# IR.net
KiCad netlist of a schematic drawn in EAGLE
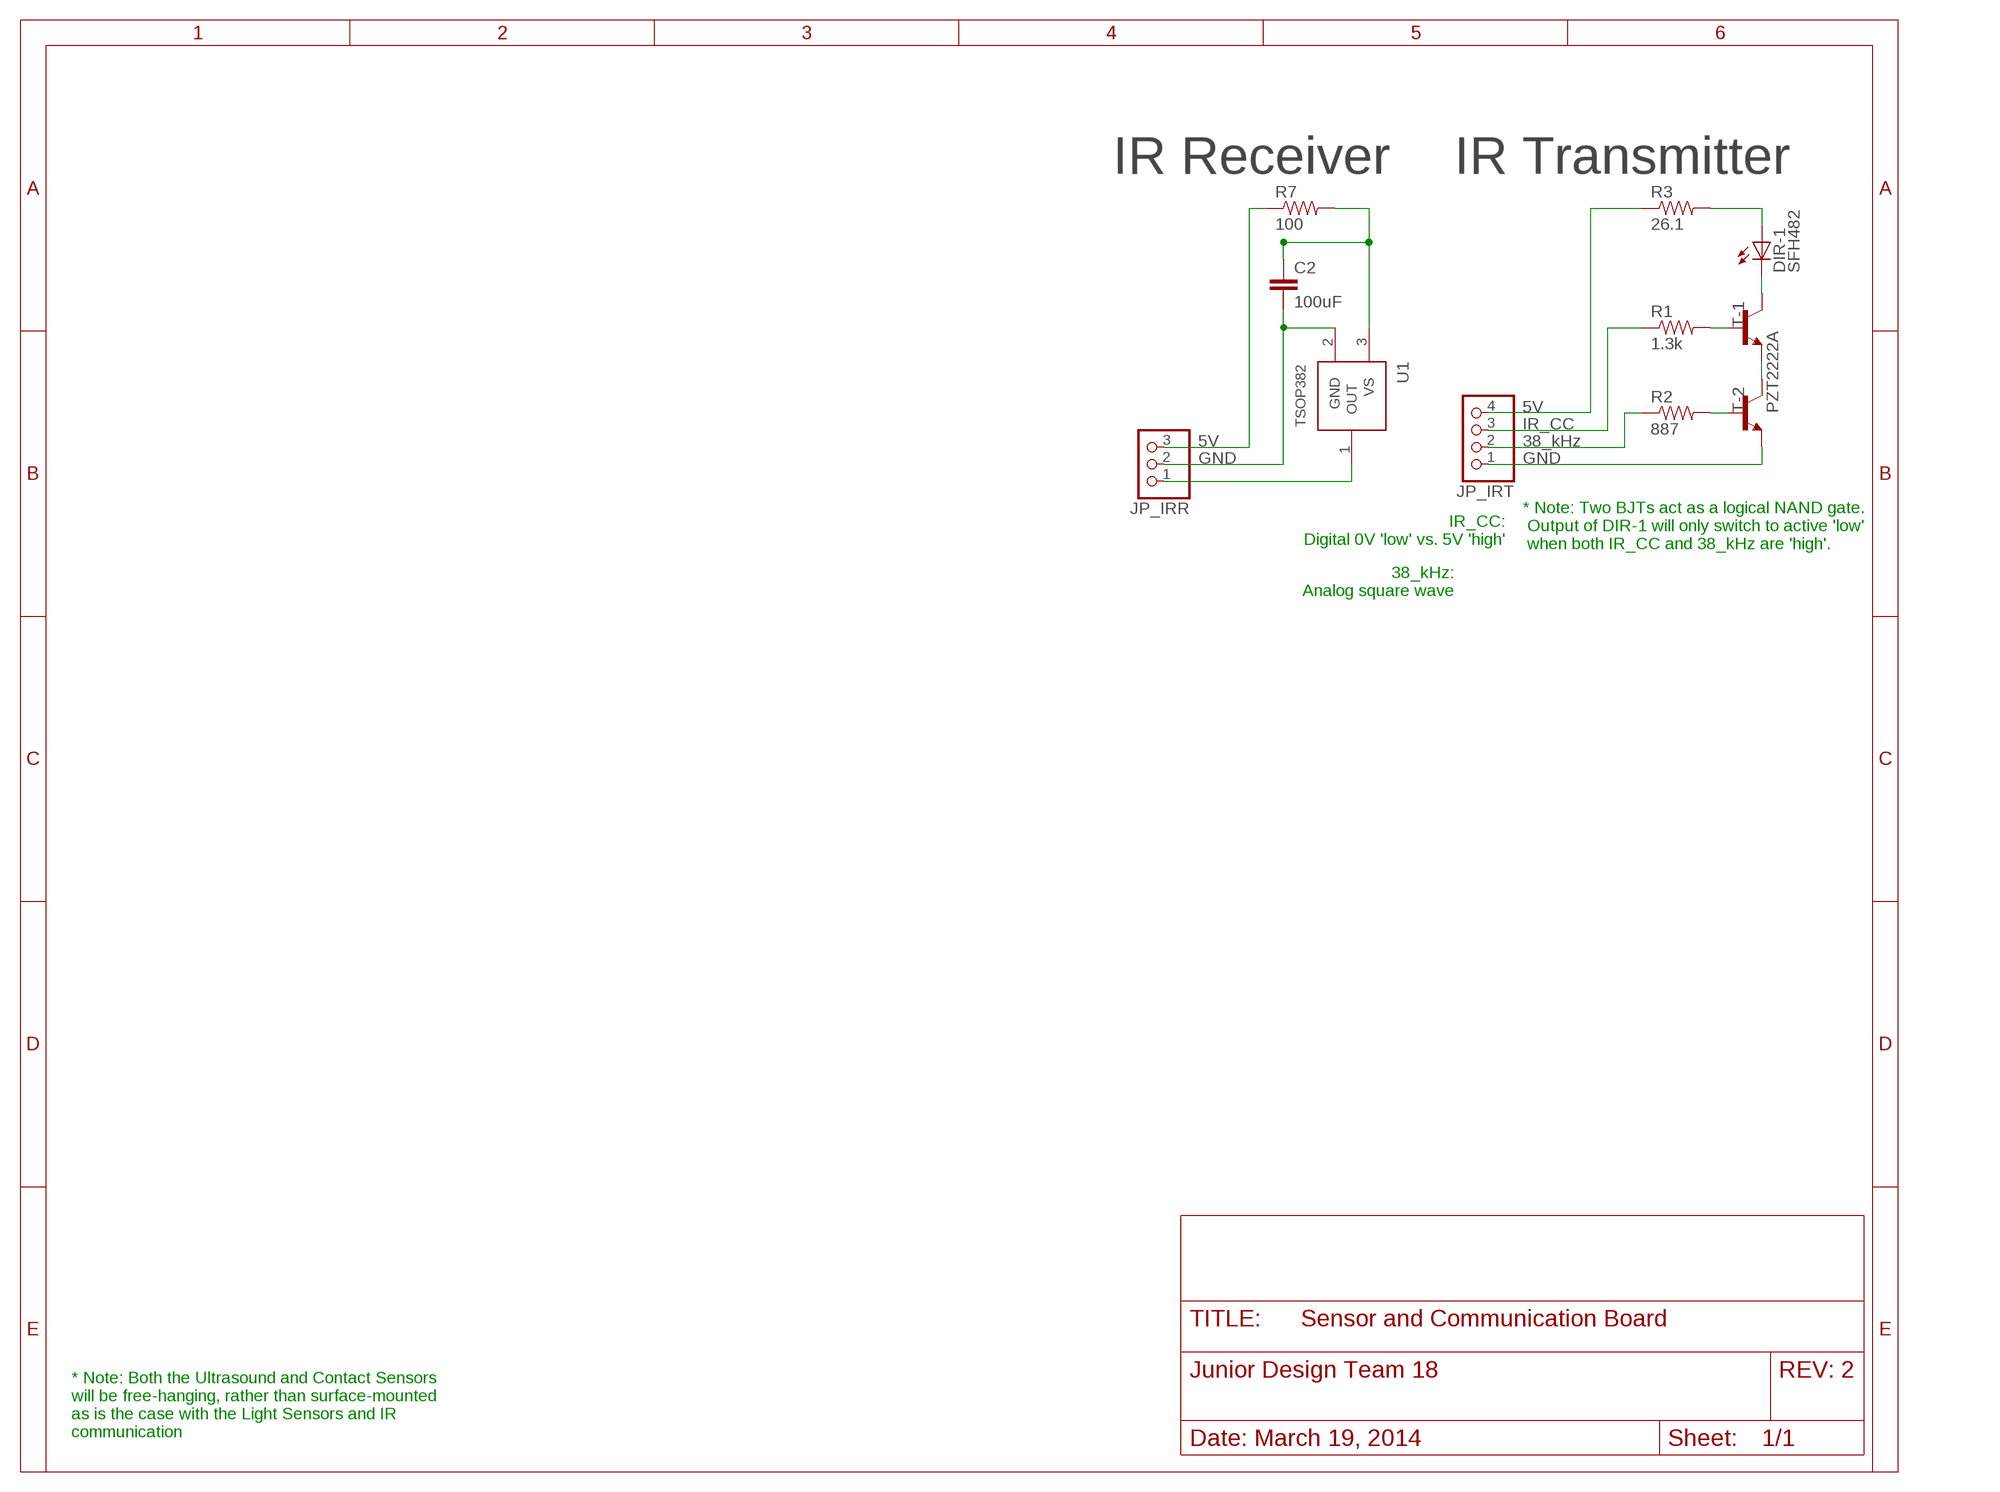
[diagram p0: schematic, sheet 1]

(export (version "E")
  (design (tool "Eeschema 10.0.6"))
  (components
    (comp (ref "C2")
      (value "100uF")
      (footprint "eagle-import:1206")
      (libsource (lib "eagle-import") (part "CAP1206"))
    )
    (comp (ref "DIR-1")
      (value "SFH482")
      (footprint "eagle-import:SFH482")
      (libsource (lib "eagle-import") (part "SFH482"))
    )
    (comp (ref "JP_IRR")
      (value "PINHD-1X3")
      (footprint "eagle-import:1X03")
      (libsource (lib "eagle-import") (part "PINHD-1X3"))
    )
    (comp (ref "JP_IRT")
      (value "PINHD-1X4")
      (footprint "eagle-import:1X04")
      (libsource (lib "eagle-import") (part "PINHD-1X4"))
    )
    (comp (ref "R1")
      (value "1.3k")
      (footprint "eagle-import:0805")
      (libsource (lib "eagle-import") (part "RESISTOR0805-RES"))
    )
    (comp (ref "R2")
      (value "887")
      (footprint "eagle-import:0805")
      (libsource (lib "eagle-import") (part "RESISTOR0805-RES"))
    )
    (comp (ref "R3")
      (value "26.1")
      (footprint "eagle-import:1206")
      (libsource (lib "eagle-import") (part "RESISTOR1206"))
    )
    (comp (ref "R7")
      (value "100")
      (footprint "eagle-import:0805")
      (libsource (lib "eagle-import") (part "RESISTOR0805-RES"))
    )
    (comp (ref "T-1")
      (value "PZT2222A")
      (footprint "eagle-import:SOT223")
      (libsource (lib "eagle-import") (part "PZT2222A"))
    )
    (comp (ref "T-2")
      (value "PZT2222A")
      (footprint "eagle-import:SOT223")
      (libsource (lib "eagle-import") (part "PZT2222A"))
    )
    (comp (ref "U1")
      (value "TSOP382")
      (footprint "eagle-import:TSOP382")
      (libsource (lib "eagle-import") (part "TSOP382"))
    )
  )
  (nets
    (net (code "1") (name "Net-(DIR-1-C)") (class "Default")
      (node (ref "DIR-1") (pin "K") (pinfunction "C_K") (pintype "passive"))
      (node (ref "T-1") (pin "2") (pinfunction "C_2") (pintype "passive"))
      (node (ref "T-1") (pin "4") (pinfunction "C_4") (pintype "passive"))
    )
    (net (code "2") (name "Net-(DIR-1-PadA)") (class "Default")
      (node (ref "DIR-1") (pin "A") (pinfunction "A_A") (pintype "passive"))
      (node (ref "R3") (pin "2") (pinfunction "2_2") (pintype "passive"))
    )
    (net (code "3") (name "Net-(JP_IRR-Pad3)") (class "Default")
      (node (ref "JP_IRR") (pin "3") (pinfunction "3_3") (pintype "passive"))
      (node (ref "R7") (pin "1") (pinfunction "1_1") (pintype "passive"))
    )
    (net (code "4") (name "Net-(JP_IRT-Pad2)") (class "Default")
      (node (ref "JP_IRT") (pin "2") (pinfunction "2_2") (pintype "passive"))
      (node (ref "R2") (pin "1") (pinfunction "1_1") (pintype "passive"))
    )
    (net (code "5") (name "Net-(JP_IRT-Pad3)") (class "Default")
      (node (ref "JP_IRT") (pin "3") (pinfunction "3_3") (pintype "passive"))
      (node (ref "R1") (pin "1") (pinfunction "1_1") (pintype "passive"))
    )
    (net (code "6") (name "Net-(JP_IRT-Pad4)") (class "Default")
      (node (ref "JP_IRT") (pin "4") (pinfunction "4_4") (pintype "passive"))
      (node (ref "R3") (pin "1") (pinfunction "1_1") (pintype "passive"))
    )
    (net (code "7") (name "Net-(T-1-B)") (class "Default")
      (node (ref "R1") (pin "2") (pinfunction "2_2") (pintype "passive"))
      (node (ref "T-1") (pin "1") (pinfunction "B_1") (pintype "passive"))
    )
    (net (code "8") (name "Net-(T-1-E)") (class "Default")
      (node (ref "T-1") (pin "3") (pinfunction "E_3") (pintype "passive"))
      (node (ref "T-2") (pin "2") (pinfunction "C_2") (pintype "passive"))
      (node (ref "T-2") (pin "4") (pinfunction "C_4") (pintype "passive"))
    )
    (net (code "9") (name "Net-(T-2-B)") (class "Default")
      (node (ref "R2") (pin "2") (pinfunction "2_2") (pintype "passive"))
      (node (ref "T-2") (pin "1") (pinfunction "B_1") (pintype "passive"))
    )
    (net (code "10") (name "Net-(T-2-E)") (class "Default")
      (node (ref "JP_IRT") (pin "1") (pinfunction "1_1") (pintype "passive"))
      (node (ref "T-2") (pin "3") (pinfunction "E_3") (pintype "passive"))
    )
    (net (code "11") (name "Net-(U1-GND)") (class "Default")
      (node (ref "C2") (pin "2") (pinfunction "2_2") (pintype "passive"))
      (node (ref "JP_IRR") (pin "2") (pinfunction "2_2") (pintype "passive"))
      (node (ref "U1") (pin "2") (pinfunction "GND_2") (pintype "bidirectional"))
    )
    (net (code "12") (name "Net-(U1-OUT)") (class "Default")
      (node (ref "JP_IRR") (pin "1") (pinfunction "1_1") (pintype "passive"))
      (node (ref "U1") (pin "1") (pinfunction "OUT_1") (pintype "bidirectional"))
    )
    (net (code "13") (name "Net-(U1-VS)") (class "Default")
      (node (ref "C2") (pin "1") (pinfunction "1_1") (pintype "passive"))
      (node (ref "R7") (pin "2") (pinfunction "2_2") (pintype "passive"))
      (node (ref "U1") (pin "3") (pinfunction "VS_3") (pintype "bidirectional"))
    )
  )
)
